# esp12power_supply.net
KiCad netlist of a schematic drawn in EAGLE
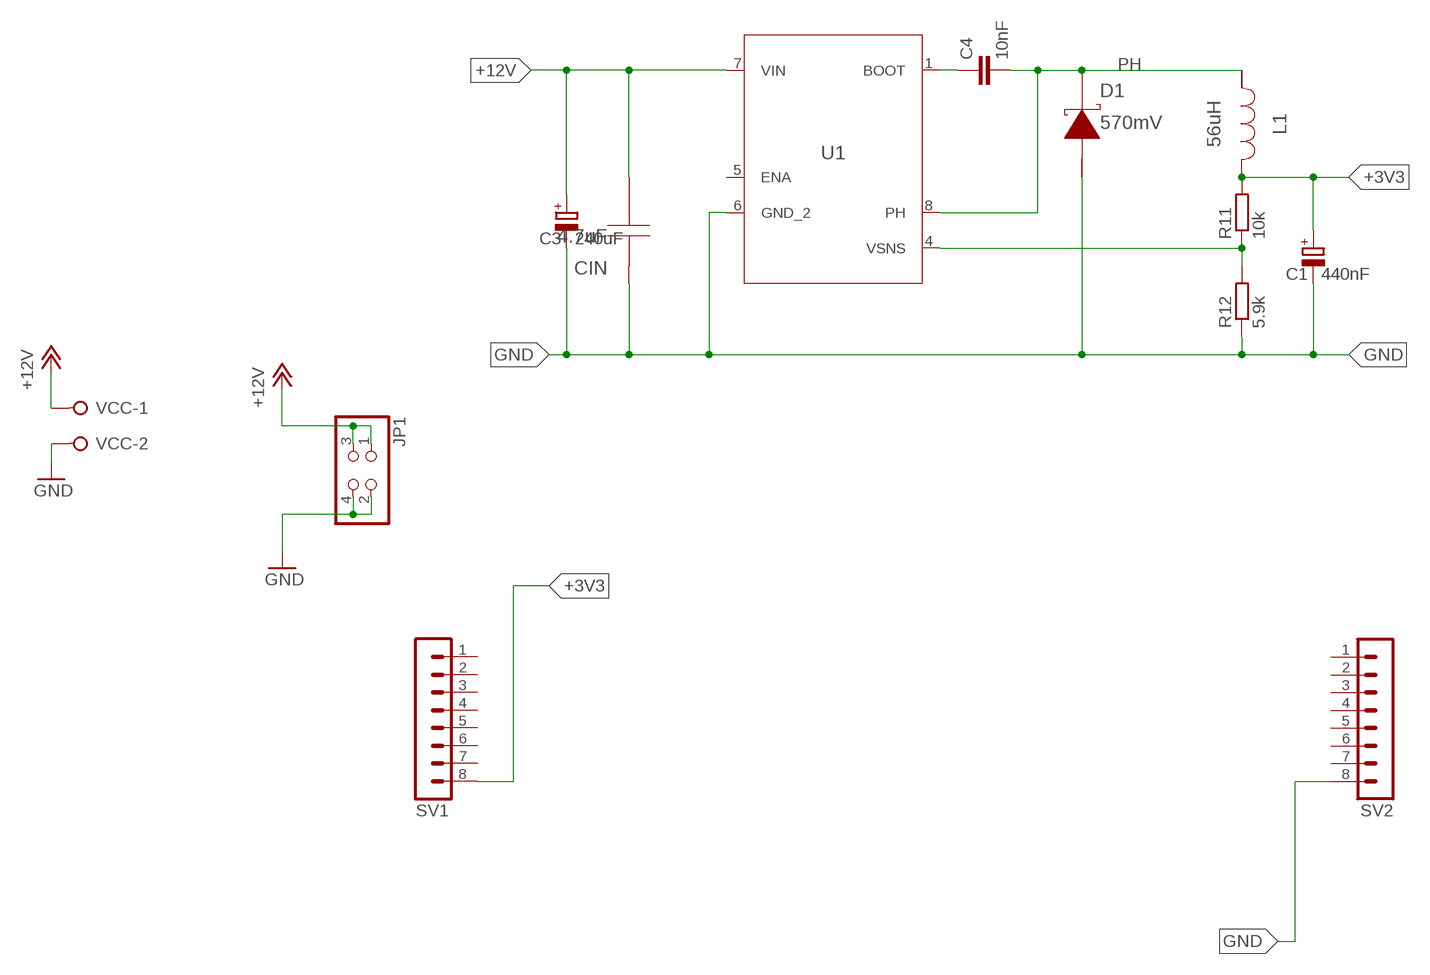
[diagram p0: schematic, sheet 1]

(export (version "E")
  (design (tool "Eeschema 10.0.6"))
  (components
    (comp (ref "C1")
      (value "440nF")
      (footprint "eagle-import:E2,5-7")
      (libsource (lib "eagle-import") (part "CPOL-EUE2.5-7"))
    )
    (comp (ref "C3")
      (value "240uF")
      (footprint "eagle-import:E2,5-7")
      (libsource (lib "eagle-import") (part "CPOL-EUE2.5-7"))
    )
    (comp (ref "C4")
      (value "10nF")
      (footprint "eagle-import:C0805")
      (libsource (lib "eagle-import") (part "C-EUC0805"))
    )
    (comp (ref "CIN")
      (value "4.7uF")
      (footprint "eagle-import:1206")
      (fields (field (name "MANUFACTURER_PART_NUMBER") "GRM31CR71H475KA12L"))
      (libsource (lib "eagle-import") (part "GRM31CR71H475KA12L"))
    )
    (comp (ref "D1")
      (value "570mV")
      (footprint "eagle-import:SMA")
      (fields (field (name "MANUFACTURER_PART_NUMBER") "B16013F"))
      (libsource (lib "eagle-import") (part "B160-13-F"))
    )
    (comp (ref "JP1")
      (value "PINHD-2X2")
      (footprint "eagle-import:2X02")
      (libsource (lib "eagle-import") (part "PINHD-2X2"))
    )
    (comp (ref "L1")
      (value "56uH")
      (footprint "eagle-import:IND_NPI75C")
      (fields (field (name "MANUFACTURER_PART_NUMBER") "NPI75C560KTRF"))
      (libsource (lib "eagle-import") (part "NPI75C560KTRF"))
    )
    (comp (ref "R11")
      (value "10k")
      (footprint "eagle-import:R0805")
      (libsource (lib "eagle-import") (part "R-EU_R0805"))
    )
    (comp (ref "R12")
      (value "5.9k")
      (footprint "eagle-import:R0805")
      (libsource (lib "eagle-import") (part "R-EU_R0805"))
    )
    (comp (ref "SV1")
      (value "MA08-1")
      (footprint "eagle-import:MA08-1")
      (libsource (lib "eagle-import") (part "MA08-1"))
    )
    (comp (ref "SV2")
      (value "MA08-1")
      (footprint "eagle-import:MA08-1")
      (libsource (lib "eagle-import") (part "MA08-1"))
    )
    (comp (ref "U1")
      (value "TPS5410DR")
      (footprint "eagle-import:M08A")
      (libsource (lib "eagle-import") (part "TPS5410DR"))
    )
    (comp (ref "VCC")
      (value "W237-02P")
      (footprint "eagle-import:W237-132")
      (libsource (lib "eagle-import") (part "W237-02P"))
    )
  )
  (nets
    (net (code "1") (name "+3V3") (class "Default")
      (node (ref "C1") (pin "+") (pinfunction "+_+") (pintype "passive"))
      (node (ref "L1") (pin "1") (pinfunction "1_1") (pintype "passive"))
      (node (ref "R11") (pin "2") (pinfunction "2_2") (pintype "passive"))
      (node (ref "SV1") (pin "8") (pinfunction "8_8") (pintype "passive"))
    )
    (net (code "2") (name "+12V") (class "Default")
      (node (ref "C3") (pin "+") (pinfunction "+_+") (pintype "passive"))
      (node (ref "CIN") (pin "2") (pinfunction "2_2") (pintype "passive"))
      (node (ref "JP1") (pin "1") (pinfunction "1_1") (pintype "passive"))
      (node (ref "JP1") (pin "3") (pinfunction "3_3") (pintype "passive"))
      (node (ref "U1") (pin "7") (pinfunction "VIN_7") (pintype "passive"))
      (node (ref "VCC") (pin "1") (pinfunction "KL_1") (pintype "passive"))
    )
    (net (code "3") (name "/PH") (class "Default")
      (node (ref "C4") (pin "2") (pinfunction "2_2") (pintype "passive"))
      (node (ref "D1") (pin "1") (pinfunction "K_1") (pintype "passive"))
      (node (ref "L1") (pin "2") (pinfunction "2_2") (pintype "passive"))
      (node (ref "U1") (pin "8") (pinfunction "PH_8") (pintype "passive"))
    )
    (net (code "4") (name "GND") (class "Default")
      (node (ref "C1") (pin "-") (pinfunction "-_-") (pintype "passive"))
      (node (ref "C3") (pin "-") (pinfunction "-_-") (pintype "passive"))
      (node (ref "CIN") (pin "1") (pinfunction "1_1") (pintype "passive"))
      (node (ref "D1") (pin "2") (pinfunction "A_2") (pintype "passive"))
      (node (ref "JP1") (pin "2") (pinfunction "2_2") (pintype "passive"))
      (node (ref "JP1") (pin "4") (pinfunction "4_4") (pintype "passive"))
      (node (ref "R12") (pin "1") (pinfunction "1_1") (pintype "passive"))
      (node (ref "SV2") (pin "8") (pinfunction "8_8") (pintype "passive"))
      (node (ref "U1") (pin "6") (pinfunction "GND_2_6") (pintype "passive"))
      (node (ref "VCC") (pin "2") (pinfunction "KL_2") (pintype "passive"))
    )
    (net (code "5") (name "Net-(U1-BOOT)") (class "Default")
      (node (ref "C4") (pin "1") (pinfunction "1_1") (pintype "passive"))
      (node (ref "U1") (pin "1") (pinfunction "BOOT_1") (pintype "passive"))
    )
    (net (code "6") (name "Net-(U1-VSNS)") (class "Default")
      (node (ref "R11") (pin "1") (pinfunction "1_1") (pintype "passive"))
      (node (ref "R12") (pin "2") (pinfunction "2_2") (pintype "passive"))
      (node (ref "U1") (pin "4") (pinfunction "VSNS_4") (pintype "passive"))
    )
    (net (code "7") (name "unconnected-(SV1-Pad1)") (class "Default")
      (node (ref "SV1") (pin "1") (pinfunction "1_1") (pintype "passive"))
    )
    (net (code "8") (name "unconnected-(SV1-Pad2)") (class "Default")
      (node (ref "SV1") (pin "2") (pinfunction "2_2") (pintype "passive"))
    )
    (net (code "9") (name "unconnected-(SV1-Pad3)") (class "Default")
      (node (ref "SV1") (pin "3") (pinfunction "3_3") (pintype "passive"))
    )
    (net (code "10") (name "unconnected-(SV1-Pad4)") (class "Default")
      (node (ref "SV1") (pin "4") (pinfunction "4_4") (pintype "passive"))
    )
    (net (code "11") (name "unconnected-(SV1-Pad5)") (class "Default")
      (node (ref "SV1") (pin "5") (pinfunction "5_5") (pintype "passive"))
    )
    (net (code "12") (name "unconnected-(SV1-Pad6)") (class "Default")
      (node (ref "SV1") (pin "6") (pinfunction "6_6") (pintype "passive"))
    )
    (net (code "13") (name "unconnected-(SV1-Pad7)") (class "Default")
      (node (ref "SV1") (pin "7") (pinfunction "7_7") (pintype "passive"))
    )
    (net (code "14") (name "unconnected-(SV2-Pad1)") (class "Default")
      (node (ref "SV2") (pin "1") (pinfunction "1_1") (pintype "passive"))
    )
    (net (code "15") (name "unconnected-(SV2-Pad2)") (class "Default")
      (node (ref "SV2") (pin "2") (pinfunction "2_2") (pintype "passive"))
    )
    (net (code "16") (name "unconnected-(SV2-Pad3)") (class "Default")
      (node (ref "SV2") (pin "3") (pinfunction "3_3") (pintype "passive"))
    )
    (net (code "17") (name "unconnected-(SV2-Pad4)") (class "Default")
      (node (ref "SV2") (pin "4") (pinfunction "4_4") (pintype "passive"))
    )
    (net (code "18") (name "unconnected-(SV2-Pad5)") (class "Default")
      (node (ref "SV2") (pin "5") (pinfunction "5_5") (pintype "passive"))
    )
    (net (code "19") (name "unconnected-(SV2-Pad6)") (class "Default")
      (node (ref "SV2") (pin "6") (pinfunction "6_6") (pintype "passive"))
    )
    (net (code "20") (name "unconnected-(SV2-Pad7)") (class "Default")
      (node (ref "SV2") (pin "7") (pinfunction "7_7") (pintype "passive"))
    )
    (net (code "21") (name "unconnected-(U1-ENA-Pad5)") (class "Default")
      (node (ref "U1") (pin "5") (pinfunction "ENA_5") (pintype "passive"))
    )
  )
)
